# Opto_sensor.net
KiCad netlist of a schematic drawn in EasyEDA
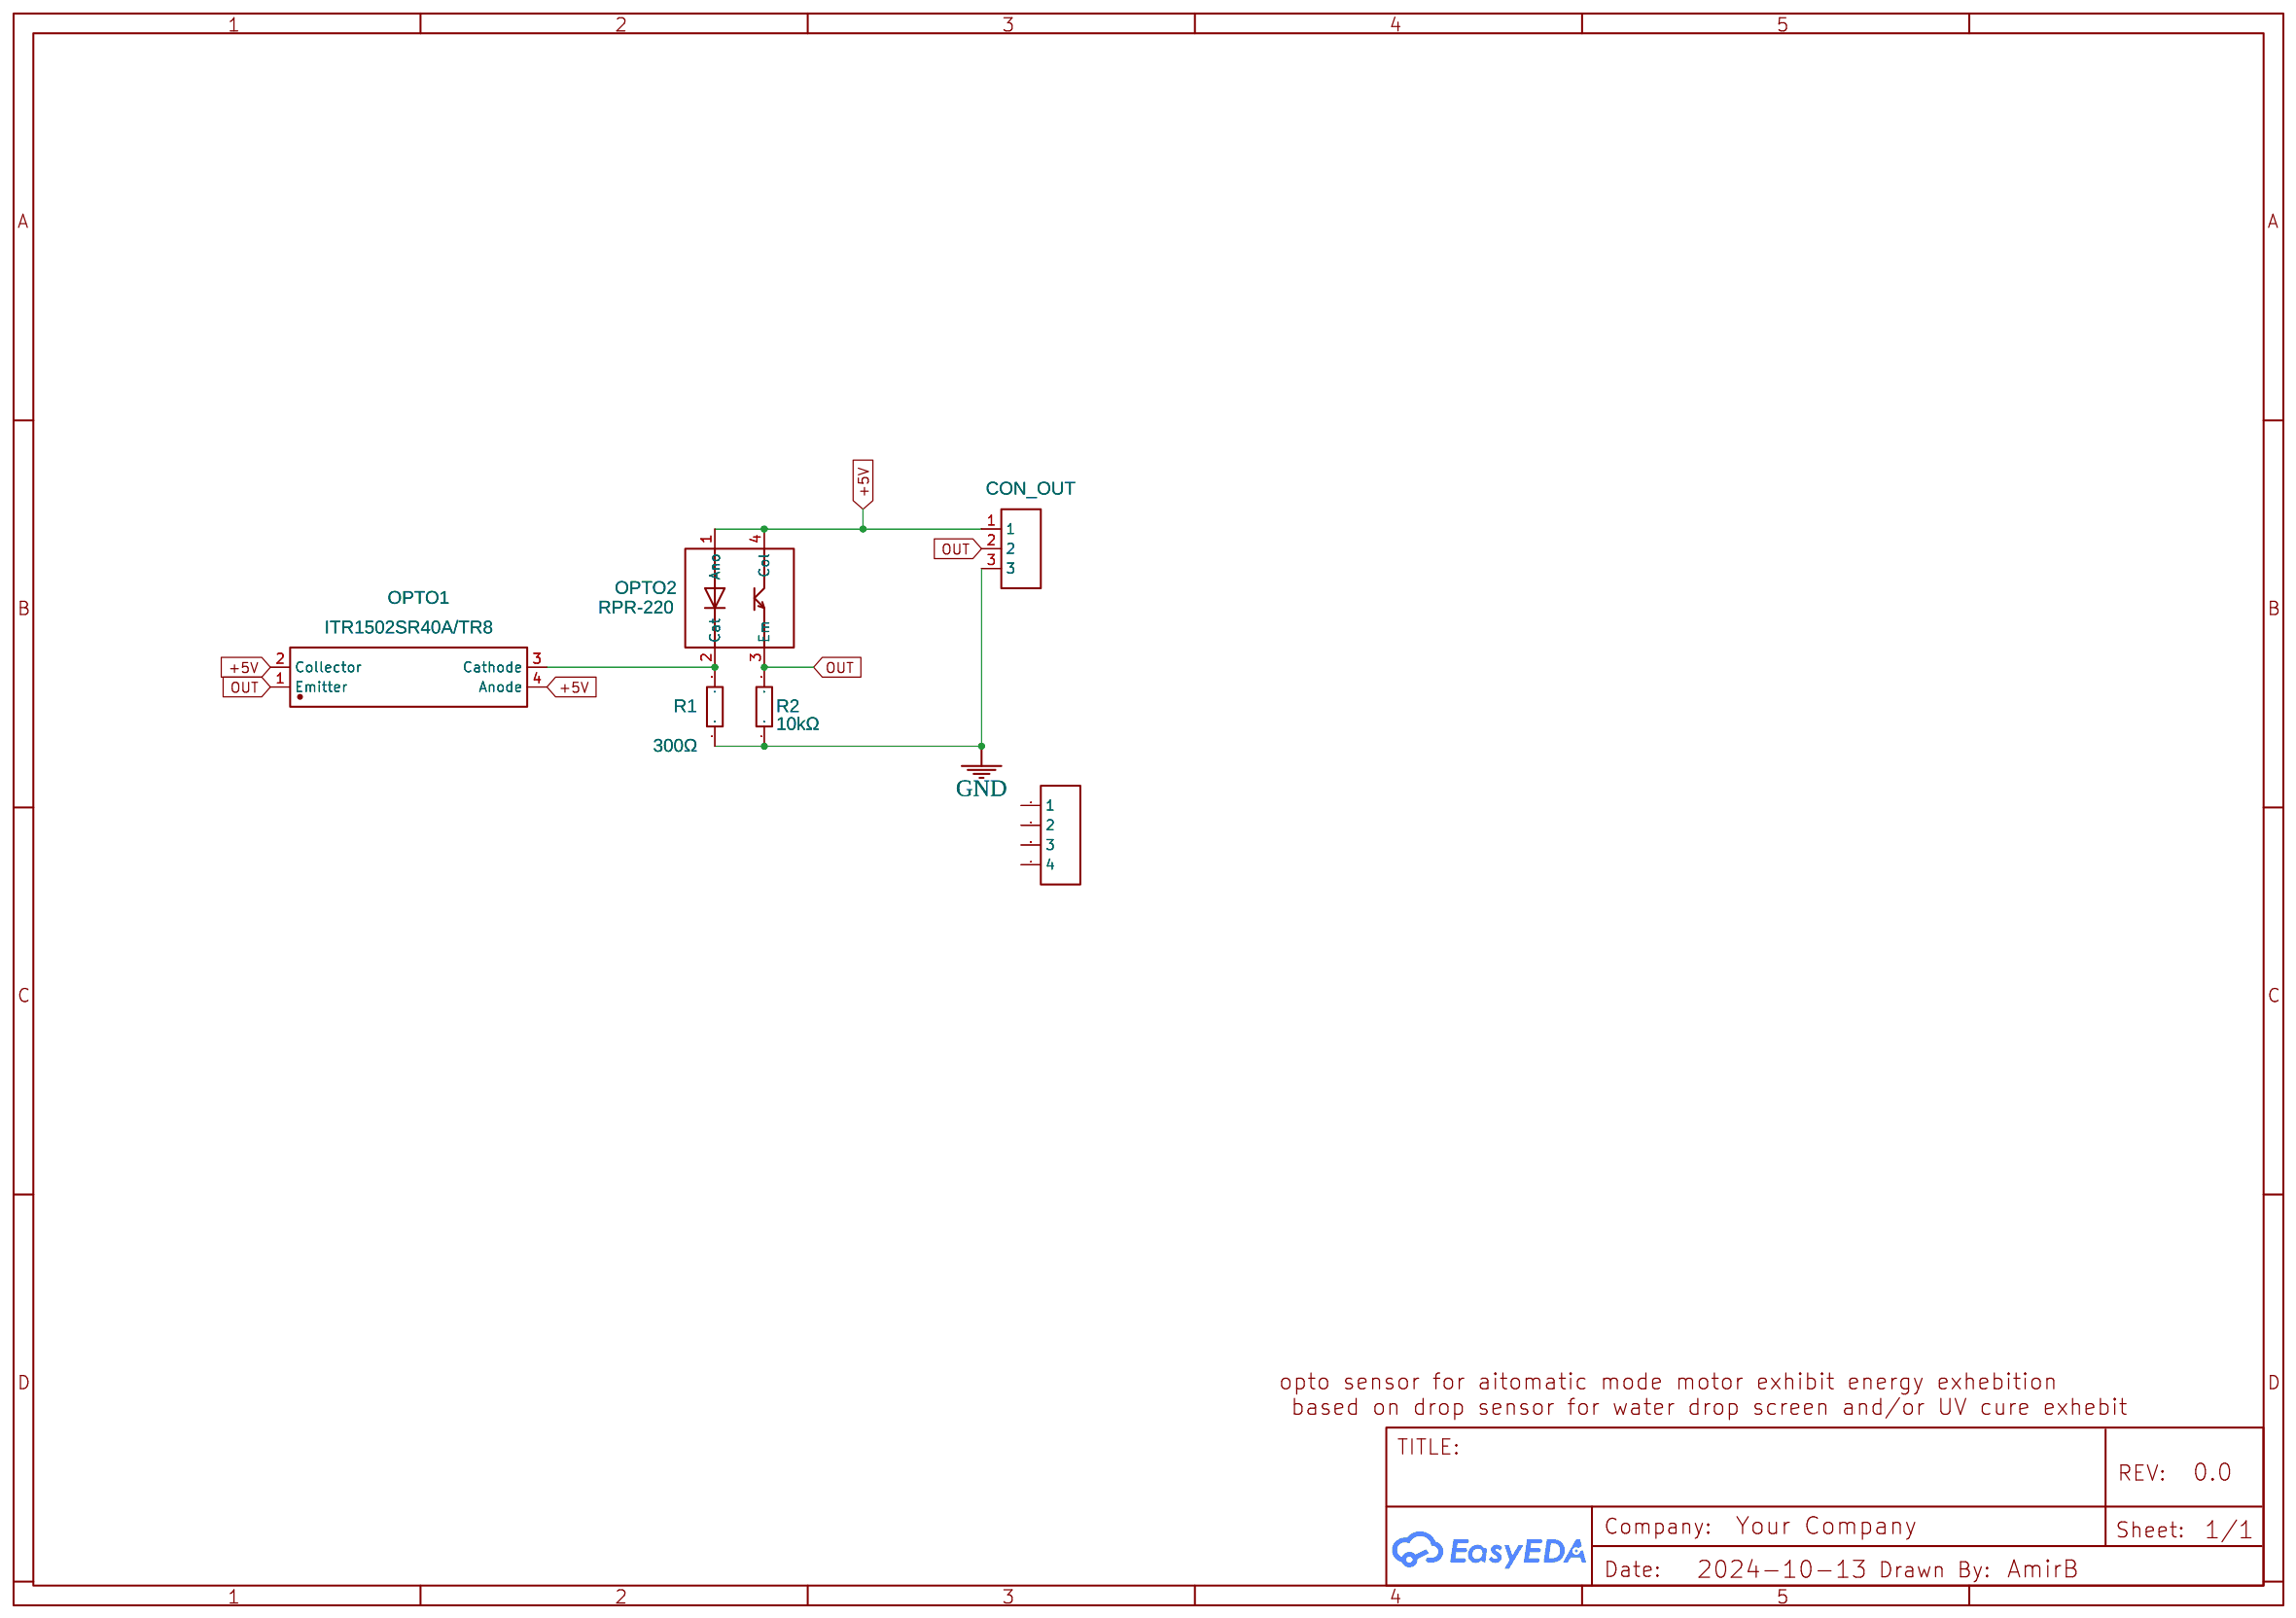
[diagram p0: schematic sheet]

(export (version "E")
  (design (tool "Eeschema 10.0.6"))
  (components
    (comp (ref "CON_OUT")
      (value "FK2510")
      (fields (field (name "Manufacturer Part") "2510-3A") (field (name "Manufacturer") "BOOMELE(博穆精密)"))
      (libsource (lib "") (part "kf2510_3A"))
    )
    (comp (ref "J1")
      (value "HDR-M-2.54_1x4")
      (fields (field (name "BOM_Supplier Part") "C124378"))
      (libsource (lib "") (part "HDR-M-2.54_1x4"))
    )
    (comp (ref "OPTO1")
      (value "ITR1502SR40A/TR8")
      (fields (field (name "Manufacturer") "EVERLIGHT(亿光)"))
      (libsource (lib "") (part "ITR1502SR40A/TR8"))
    )
    (comp (ref "OPTO2")
      (value "RPR-220")
      (fields (field (name "Manufacturer") "ROHM(罗姆)"))
      (libsource (lib "") (part "RPR-220"))
    )
    (comp (ref "R1")
      (value "300Ω")
      (fields
        (field (name "Manufacturer Part") "0603WAF3000T5E")
        (field (name "Manufacturer") "UNI-ROYAL(厚声)")
      )
      (libsource (lib "") (part "0603WAF3000T5E"))
    )
    (comp (ref "R2")
      (value "10kΩ")
      (fields
        (field (name "Manufacturer Part") "0603WAF1002T5E")
        (field (name "Manufacturer") "UNI-ROYAL(厚声)")
      )
      (libsource (lib "") (part "0603WAF1002T5E"))
    )
  )
  (nets
    (net (code "1") (name "+5V") (class "Default")
      (node (ref "CON_OUT") (pin "1") (pinfunction "1_1") (pintype "unspecified"))
      (node (ref "OPTO1") (pin "2") (pinfunction "Collector_2") (pintype "unspecified"))
      (node (ref "OPTO1") (pin "4") (pinfunction "Anode_4") (pintype "unspecified"))
      (node (ref "OPTO2") (pin "1") (pinfunction "Ano_1") (pintype "unspecified"))
      (node (ref "OPTO2") (pin "4") (pinfunction "Col_4") (pintype "unspecified"))
    )
    (net (code "2") (name "GND") (class "Default")
      (node (ref "CON_OUT") (pin "3") (pinfunction "3_3") (pintype "unspecified"))
      (node (ref "R1") (pin "1") (pinfunction "1_1") (pintype "input"))
      (node (ref "R2") (pin "1") (pinfunction "1_1") (pintype "input"))
    )
    (net (code "3") (name "Net-(OPTO1-Cathode)") (class "Default")
      (node (ref "OPTO1") (pin "3") (pinfunction "Cathode_3") (pintype "unspecified"))
      (node (ref "OPTO2") (pin "2") (pinfunction "Cat_2") (pintype "unspecified"))
      (node (ref "R1") (pin "2") (pinfunction "2_2") (pintype "input"))
    )
    (net (code "4") (name "OUT") (class "Default")
      (node (ref "CON_OUT") (pin "2") (pinfunction "2_2") (pintype "unspecified"))
      (node (ref "OPTO1") (pin "1") (pinfunction "Emitter_1") (pintype "unspecified"))
      (node (ref "OPTO2") (pin "3") (pinfunction "Em_3") (pintype "unspecified"))
      (node (ref "R2") (pin "2") (pinfunction "2_2") (pintype "input"))
    )
    (net (code "5") (name "unconnected-(J1-Pad1)") (class "Default")
      (node (ref "J1") (pin "1") (pinfunction "1_1") (pintype "unspecified"))
    )
    (net (code "6") (name "unconnected-(J1-Pad2)") (class "Default")
      (node (ref "J1") (pin "2") (pinfunction "2_2") (pintype "unspecified"))
    )
    (net (code "7") (name "unconnected-(J1-Pad3)") (class "Default")
      (node (ref "J1") (pin "3") (pinfunction "3_3") (pintype "unspecified"))
    )
    (net (code "8") (name "unconnected-(J1-Pad4)") (class "Default")
      (node (ref "J1") (pin "4") (pinfunction "4_4") (pintype "unspecified"))
    )
  )
)
